# V2.net
KiCad netlist of a schematic drawn in EAGLE
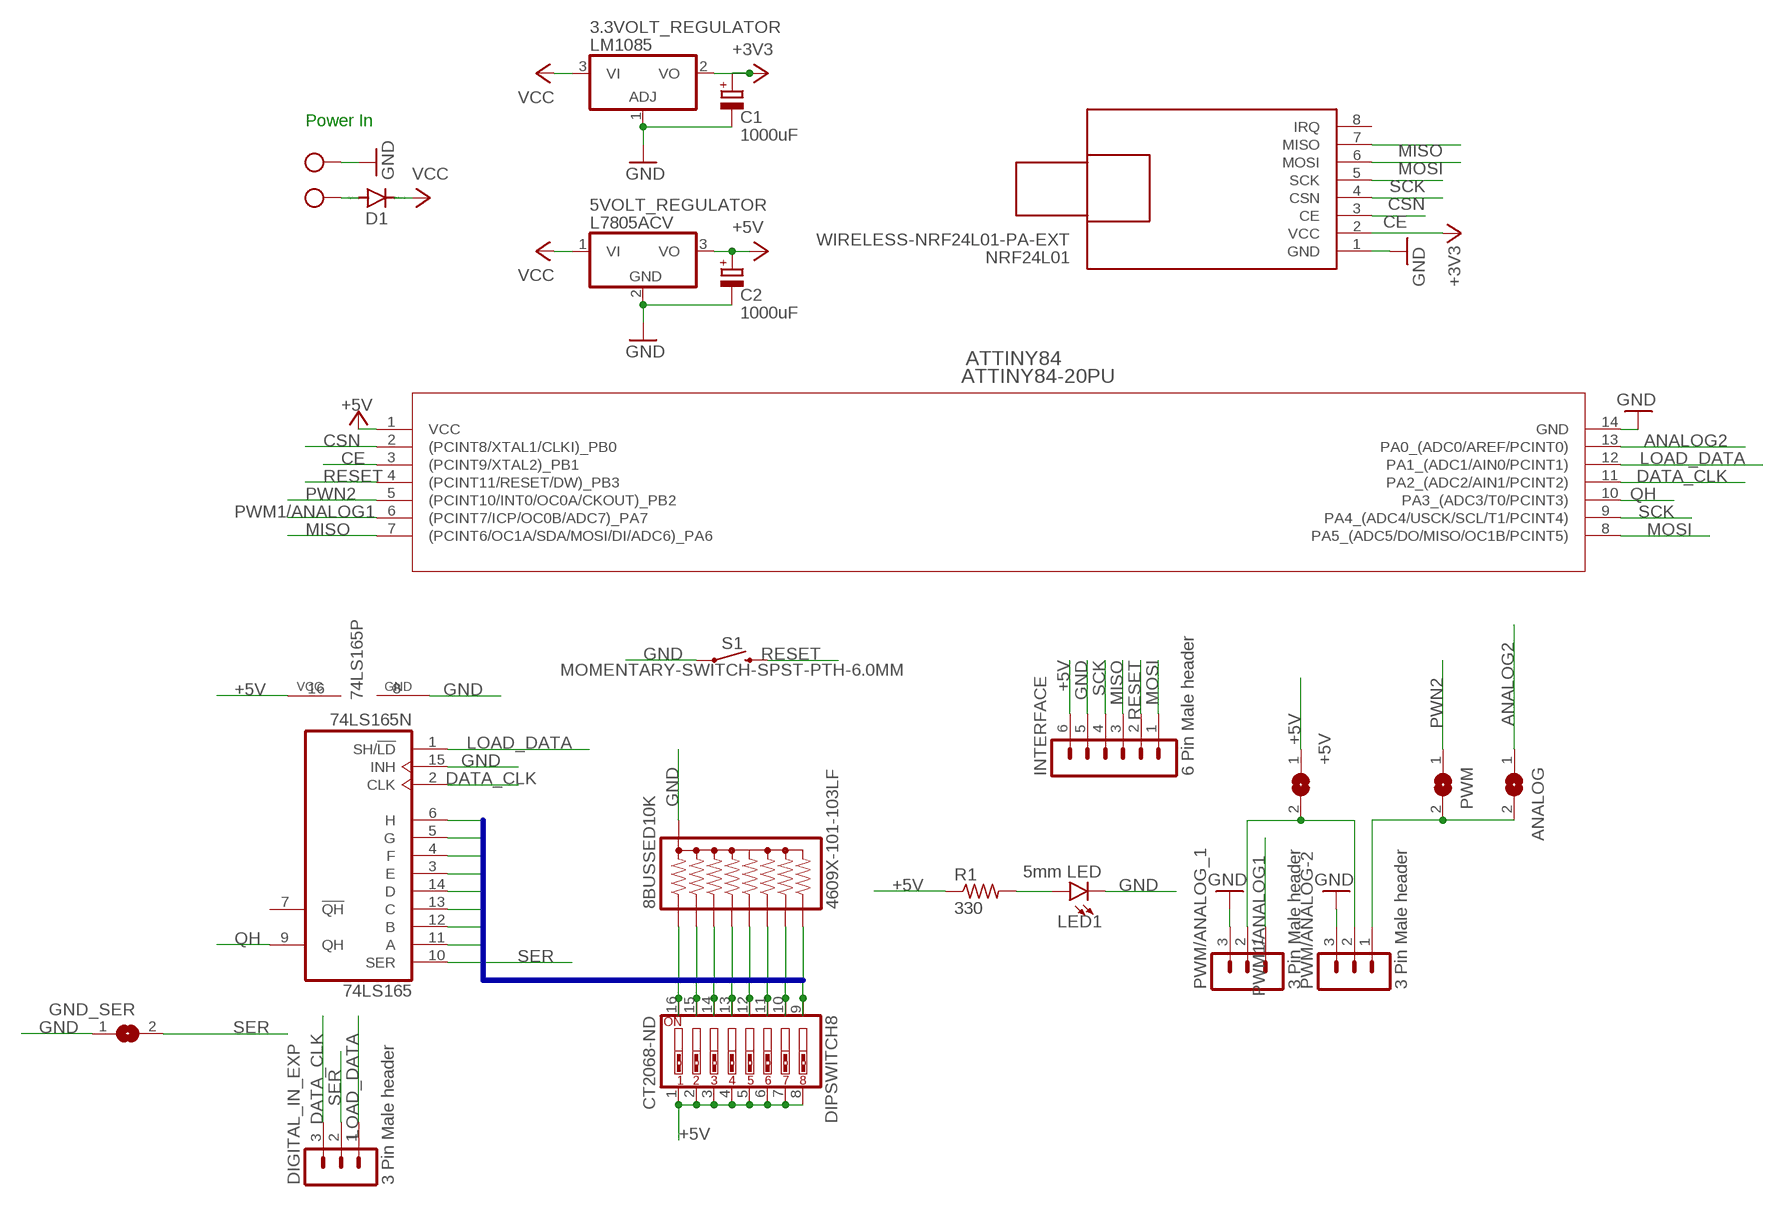
[diagram p0: schematic, sheet 1]

(export (version "E")
  (design (tool "Eeschema 10.0.6"))
  (components
    (comp (ref "+5V")
      (value "SJW")
      (footprint "eagle-import:SJW")
      (libsource (lib "eagle-import") (part "SJW"))
    )
    (comp (ref "3.3VOLT_REGULATOR")
      (value "LM1085")
      (footprint "eagle-import:TO220V")
      (libsource (lib "eagle-import") (part "MC33269?T-12"))
    )
    (comp (ref "5VOLT_REGULATOR")
      (value "L7805ACV")
      (footprint "eagle-import:TO220V")
      (libsource (lib "eagle-import") (part "78TV8"))
    )
    (comp (ref "8BUSSED10K")
      (value "4609X-101-103LF")
      (footprint "eagle-import:RPACK-SIP-PTH-8")
      (libsource (lib "eagle-import") (part "10K_BUSSED_8"))
    )
    (comp (ref "74LS165")
      (value "74LS165N")
      (footprint "eagle-import:DIL16")
      (libsource (lib "eagle-import") (part "74165NLS"))
    )
    (comp (ref "ANALOG")
      (value "SJW")
      (footprint "eagle-import:SJW")
      (libsource (lib "eagle-import") (part "SJW"))
    )
    (comp (ref "ATTINY84")
      (value "ATTINY84-20PU")
      (footprint "eagle-import:14P3")
      (fields (field (name "MANUFACTURER_PART_NUMBER") "ATTINY8420PU"))
      (libsource (lib "eagle-import") (part "ATTINY84-20PU"))
    )
    (comp (ref "C1")
      (value "1000uF")
      (footprint "eagle-import:E2,5-6")
      (libsource (lib "eagle-import") (part "CPOL-EUE2.5-6"))
    )
    (comp (ref "C2")
      (value "1000uF")
      (footprint "eagle-import:E2,5-6")
      (libsource (lib "eagle-import") (part "CPOL-EUE2.5-6"))
    )
    (comp (ref "D1")
      (value "1N5060GP")
      (footprint "eagle-import:DO15-12")
      (libsource (lib "eagle-import") (part "1N5060GP"))
    )
    (comp (ref "DIGITAL_IN_EXP")
      (value "3 Pin Male header")
      (footprint "eagle-import:MA03-1")
      (libsource (lib "eagle-import") (part "MA03-1"))
    )
    (comp (ref "DIPSWITCH8")
      (value "CT2068-ND")
      (footprint "eagle-import:EDG-08")
      (libsource (lib "eagle-import") (part "SW_DIP-8"))
    )
    (comp (ref "GND_SER")
      (value "SJW")
      (footprint "eagle-import:SJW")
      (libsource (lib "eagle-import") (part "SJW"))
    )
    (comp (ref "INTERFACE")
      (value "6 Pin Male header")
      (footprint "eagle-import:MA06-1")
      (libsource (lib "eagle-import") (part "MA06-1"))
    )
    (comp (ref "LED1")
      (value "5mm LED")
      (footprint "eagle-import:LED_5MM")
      (libsource (lib "eagle-import") (part "LED5MM"))
    )
    (comp (ref "NRF24L01")
      (value "WIRELESS-NRF24L01-PA-EXT")
      (footprint "eagle-import:WIRELESS-NRF24L01-PA-EXT")
      (libsource (lib "eagle-import") (part "WIRELESS-NRF24L01-PA-EXT"))
    )
    (comp (ref "PWM")
      (value "SJW")
      (footprint "eagle-import:SJW")
      (libsource (lib "eagle-import") (part "SJW"))
    )
    (comp (ref "PWM/ANALOG-2")
      (value "3 Pin Male header")
      (footprint "eagle-import:MA03-1")
      (libsource (lib "eagle-import") (part "MA03-1"))
    )
    (comp (ref "PWM/ANALOG_1")
      (value "3 Pin Male header")
      (footprint "eagle-import:MA03-1")
      (libsource (lib "eagle-import") (part "MA03-1"))
    )
    (comp (ref "R1")
      (value "330")
      (footprint "eagle-import:0204_7")
      (libsource (lib "eagle-import") (part "R-US_0204/7"))
    )
    (comp (ref "S1")
      (value "MOMENTARY-SWITCH-SPST-PTH-6.0MM")
      (footprint "eagle-import:TACTILE_SWITCH_PTH_6.0MM")
      (libsource (lib "eagle-import") (part "MOMENTARY-SWITCH-SPST-PTH-6.0MM"))
    )
    (comp (ref "X1")
      (value "MKDSN1,5/2-5,08")
      (footprint "eagle-import:MKDSN1,5_2-5,08")
      (libsource (lib "eagle-import") (part "MKDSN1,5/2-5,08"))
    )
  )
  (nets
    (net (code "1") (name "+3V3") (class "Default")
      (node (ref "3.3VOLT_REGULATOR") (pin "2") (pinfunction "VO_2") (pintype "passive"))
      (node (ref "C1") (pin "+") (pinfunction "+_+") (pintype "passive"))
      (node (ref "NRF24L01") (pin "2") (pinfunction "VCC_2") (pintype "power_in"))
    )
    (net (code "2") (name "+5V") (class "Default")
      (node (ref "+5V") (pin "1") (pinfunction "1_1") (pintype "passive"))
      (node (ref "5VOLT_REGULATOR") (pin "3") (pinfunction "VO_3") (pintype "passive"))
      (node (ref "74LS165") (pin "16") (pinfunction "VCC_16") (pintype "power_in"))
      (node (ref "ATTINY84") (pin "1") (pinfunction "VCC_1") (pintype "power_in"))
      (node (ref "C2") (pin "+") (pinfunction "+_+") (pintype "passive"))
      (node (ref "DIPSWITCH8") (pin "1") (pinfunction "1_1") (pintype "passive"))
      (node (ref "DIPSWITCH8") (pin "2") (pinfunction "2_2") (pintype "passive"))
      (node (ref "DIPSWITCH8") (pin "3") (pinfunction "3_3") (pintype "passive"))
      (node (ref "DIPSWITCH8") (pin "4") (pinfunction "4_4") (pintype "passive"))
      (node (ref "DIPSWITCH8") (pin "5") (pinfunction "5_5") (pintype "passive"))
      (node (ref "DIPSWITCH8") (pin "6") (pinfunction "6_6") (pintype "passive"))
      (node (ref "DIPSWITCH8") (pin "7") (pinfunction "7_7") (pintype "passive"))
      (node (ref "DIPSWITCH8") (pin "8") (pinfunction "8_8") (pintype "passive"))
      (node (ref "INTERFACE") (pin "6") (pinfunction "6_6") (pintype "passive"))
      (node (ref "R1") (pin "1") (pinfunction "1_1") (pintype "passive"))
    )
    (net (code "3") (name "/ANALOG2") (class "Default")
      (node (ref "ANALOG") (pin "1") (pinfunction "1_1") (pintype "passive"))
      (node (ref "ATTINY84") (pin "13") (pinfunction "PA0_(ADC0/AREF/PCINT0)_13") (pintype "bidirectional"))
    )
    (net (code "4") (name "/BIT0") (class "Default")
      (node (ref "74LS165") (pin "11") (pinfunction "A_11") (pintype "input"))
      (node (ref "8BUSSED10K") (pin "P$2") (pinfunction "2_P$2") (pintype "passive"))
      (node (ref "DIPSWITCH8") (pin "16") (pinfunction "16_16") (pintype "passive"))
    )
    (net (code "5") (name "/BIT1") (class "Default")
      (node (ref "74LS165") (pin "12") (pinfunction "B_12") (pintype "input"))
      (node (ref "8BUSSED10K") (pin "P$3") (pinfunction "3_P$3") (pintype "passive"))
      (node (ref "DIPSWITCH8") (pin "15") (pinfunction "15_15") (pintype "passive"))
    )
    (net (code "6") (name "/BIT2") (class "Default")
      (node (ref "74LS165") (pin "13") (pinfunction "C_13") (pintype "input"))
      (node (ref "8BUSSED10K") (pin "P$4") (pinfunction "4_P$4") (pintype "passive"))
      (node (ref "DIPSWITCH8") (pin "14") (pinfunction "14_14") (pintype "passive"))
    )
    (net (code "7") (name "/BIT3") (class "Default")
      (node (ref "74LS165") (pin "14") (pinfunction "D_14") (pintype "input"))
      (node (ref "8BUSSED10K") (pin "P$5") (pinfunction "5_P$5") (pintype "passive"))
      (node (ref "DIPSWITCH8") (pin "13") (pinfunction "13_13") (pintype "passive"))
    )
    (net (code "8") (name "/BIT4") (class "Default")
      (node (ref "74LS165") (pin "3") (pinfunction "E_3") (pintype "input"))
      (node (ref "8BUSSED10K") (pin "P$6") (pinfunction "6_P$6") (pintype "passive"))
      (node (ref "DIPSWITCH8") (pin "12") (pinfunction "12_12") (pintype "passive"))
    )
    (net (code "9") (name "/BIT5") (class "Default")
      (node (ref "74LS165") (pin "4") (pinfunction "F_4") (pintype "input"))
      (node (ref "8BUSSED10K") (pin "P$7") (pinfunction "7_P$7") (pintype "passive"))
      (node (ref "DIPSWITCH8") (pin "11") (pinfunction "11_11") (pintype "passive"))
    )
    (net (code "10") (name "/BIT6") (class "Default")
      (node (ref "74LS165") (pin "5") (pinfunction "G_5") (pintype "input"))
      (node (ref "8BUSSED10K") (pin "P$8") (pinfunction "8_P$8") (pintype "passive"))
      (node (ref "DIPSWITCH8") (pin "10") (pinfunction "10_10") (pintype "passive"))
    )
    (net (code "11") (name "/BIT7") (class "Default")
      (node (ref "74LS165") (pin "6") (pinfunction "H_6") (pintype "input"))
      (node (ref "8BUSSED10K") (pin "P$9") (pinfunction "9_P$9") (pintype "passive"))
      (node (ref "DIPSWITCH8") (pin "9") (pinfunction "9_9") (pintype "passive"))
    )
    (net (code "12") (name "/CE") (class "Default")
      (node (ref "ATTINY84") (pin "3") (pinfunction "(PCINT9/XTAL2)_PB1_3") (pintype "bidirectional"))
      (node (ref "NRF24L01") (pin "3") (pinfunction "CE_3") (pintype "bidirectional"))
    )
    (net (code "13") (name "/CSN") (class "Default")
      (node (ref "ATTINY84") (pin "2") (pinfunction "(PCINT8/XTAL1/CLKI)_PB0_2") (pintype "bidirectional"))
      (node (ref "NRF24L01") (pin "4") (pinfunction "CSN_4") (pintype "bidirectional"))
    )
    (net (code "14") (name "/DATA_CLK") (class "Default")
      (node (ref "74LS165") (pin "2") (pinfunction "CLK_2") (pintype "input"))
      (node (ref "ATTINY84") (pin "11") (pinfunction "PA2_(ADC2/AIN1/PCINT2)_11") (pintype "bidirectional"))
      (node (ref "DIGITAL_IN_EXP") (pin "3") (pinfunction "3_3") (pintype "passive"))
    )
    (net (code "15") (name "/LOAD_DATA") (class "Default")
      (node (ref "74LS165") (pin "1") (pinfunction "SH/~{LD}_1") (pintype "input"))
      (node (ref "ATTINY84") (pin "12") (pinfunction "PA1_(ADC1/AIN0/PCINT1)_12") (pintype "bidirectional"))
      (node (ref "DIGITAL_IN_EXP") (pin "1") (pinfunction "1_1") (pintype "passive"))
    )
    (net (code "16") (name "/MISO") (class "Default")
      (node (ref "ATTINY84") (pin "7") (pinfunction "(PCINT6/OC1A/SDA/MOSI/DI/ADC6)_PA6_7") (pintype "bidirectional"))
      (node (ref "INTERFACE") (pin "3") (pinfunction "3_3") (pintype "passive"))
      (node (ref "NRF24L01") (pin "7") (pinfunction "MISO_7") (pintype "bidirectional"))
    )
    (net (code "17") (name "/MOSI") (class "Default")
      (node (ref "ATTINY84") (pin "8") (pinfunction "PA5_(ADC5/DO/MISO/OC1B/PCINT5)_8") (pintype "bidirectional"))
      (node (ref "INTERFACE") (pin "1") (pinfunction "1_1") (pintype "passive"))
      (node (ref "NRF24L01") (pin "6") (pinfunction "MOSI_6") (pintype "bidirectional"))
    )
    (net (code "18") (name "/PWM1{slash}ANALOG1") (class "Default")
      (node (ref "ATTINY84") (pin "6") (pinfunction "(PCINT7/ICP/OC0B/ADC7)_PA7_6") (pintype "bidirectional"))
      (node (ref "PWM/ANALOG_1") (pin "1") (pinfunction "1_1") (pintype "passive"))
    )
    (net (code "19") (name "/PWN2") (class "Default")
      (node (ref "ATTINY84") (pin "5") (pinfunction "(PCINT10/INT0/OC0A/CKOUT)_PB2_5") (pintype "bidirectional"))
      (node (ref "PWM") (pin "1") (pinfunction "1_1") (pintype "passive"))
    )
    (net (code "20") (name "/QH") (class "Default")
      (node (ref "74LS165") (pin "9") (pinfunction "QH_9") (pintype "output"))
      (node (ref "ATTINY84") (pin "10") (pinfunction "PA3_(ADC3/T0/PCINT3)_10") (pintype "bidirectional"))
    )
    (net (code "21") (name "/RESET") (class "Default")
      (node (ref "ATTINY84") (pin "4") (pinfunction "(PCINT11/RESET/DW)_PB3_4") (pintype "bidirectional"))
      (node (ref "INTERFACE") (pin "2") (pinfunction "2_2") (pintype "passive"))
      (node (ref "S1") (pin "3") (pinfunction "2_3") (pintype "passive"))
    )
    (net (code "22") (name "/SCK") (class "Default")
      (node (ref "ATTINY84") (pin "9") (pinfunction "PA4_(ADC4/USCK/SCL/T1/PCINT4)_9") (pintype "bidirectional"))
      (node (ref "INTERFACE") (pin "4") (pinfunction "4_4") (pintype "passive"))
      (node (ref "NRF24L01") (pin "5") (pinfunction "SCK_5") (pintype "bidirectional"))
    )
    (net (code "23") (name "/SER") (class "Default")
      (node (ref "74LS165") (pin "10") (pinfunction "SER_10") (pintype "input"))
      (node (ref "DIGITAL_IN_EXP") (pin "2") (pinfunction "2_2") (pintype "passive"))
      (node (ref "GND_SER") (pin "2") (pinfunction "2_2") (pintype "passive"))
    )
    (net (code "24") (name "GND") (class "Default")
      (node (ref "3.3VOLT_REGULATOR") (pin "1") (pinfunction "ADJ_1") (pintype "input"))
      (node (ref "5VOLT_REGULATOR") (pin "2") (pinfunction "GND_2") (pintype "passive"))
      (node (ref "74LS165") (pin "15") (pinfunction "INH_15") (pintype "input"))
      (node (ref "74LS165") (pin "8") (pinfunction "GND_8") (pintype "power_in"))
      (node (ref "8BUSSED10K") (pin "P$1") (pinfunction "1_P$1") (pintype "passive"))
      (node (ref "ATTINY84") (pin "14") (pinfunction "GND_14") (pintype "power_in"))
      (node (ref "C1") (pin "-") (pinfunction "-_-") (pintype "passive"))
      (node (ref "C2") (pin "-") (pinfunction "-_-") (pintype "passive"))
      (node (ref "GND_SER") (pin "1") (pinfunction "1_1") (pintype "passive"))
      (node (ref "INTERFACE") (pin "5") (pinfunction "5_5") (pintype "passive"))
      (node (ref "LED1") (pin "K") (pinfunction "C_K") (pintype "passive"))
      (node (ref "NRF24L01") (pin "1") (pinfunction "GND_1") (pintype "power_in"))
      (node (ref "PWM/ANALOG-2") (pin "3") (pinfunction "3_3") (pintype "passive"))
      (node (ref "PWM/ANALOG_1") (pin "3") (pinfunction "3_3") (pintype "passive"))
      (node (ref "S1") (pin "1") (pinfunction "1_1") (pintype "passive"))
      (node (ref "X1") (pin "2") (pinfunction "KL_2") (pintype "passive"))
    )
    (net (code "25") (name "Net-(+5V-Pad2)") (class "Default")
      (node (ref "+5V") (pin "2") (pinfunction "2_2") (pintype "passive"))
      (node (ref "PWM/ANALOG-2") (pin "2") (pinfunction "2_2") (pintype "passive"))
      (node (ref "PWM/ANALOG_1") (pin "2") (pinfunction "2_2") (pintype "passive"))
    )
    (net (code "26") (name "Net-(ANALOG-Pad2)") (class "Default")
      (node (ref "ANALOG") (pin "2") (pinfunction "2_2") (pintype "passive"))
      (node (ref "PWM") (pin "2") (pinfunction "2_2") (pintype "passive"))
      (node (ref "PWM/ANALOG-2") (pin "1") (pinfunction "1_1") (pintype "passive"))
    )
    (net (code "27") (name "Net-(LED1-PadA)") (class "Default")
      (node (ref "LED1") (pin "A") (pinfunction "A_A") (pintype "passive"))
      (node (ref "R1") (pin "2") (pinfunction "2_2") (pintype "passive"))
    )
    (net (code "28") (name "Net-(X1A-KL)") (class "Default")
      (node (ref "D1") (pin "A") (pinfunction "A_A") (pintype "passive"))
      (node (ref "X1") (pin "1") (pinfunction "KL_1") (pintype "passive"))
    )
    (net (code "29") (name "VCC") (class "Default")
      (node (ref "3.3VOLT_REGULATOR") (pin "3") (pinfunction "VI_3") (pintype "input"))
      (node (ref "5VOLT_REGULATOR") (pin "1") (pinfunction "VI_1") (pintype "input"))
      (node (ref "D1") (pin "C") (pinfunction "C_C") (pintype "passive"))
    )
    (net (code "30") (name "unconnected-(74LS165A-~{QH}-Pad7)") (class "Default")
      (node (ref "74LS165") (pin "7") (pinfunction "~{QH}_7") (pintype "output"))
    )
    (net (code "31") (name "unconnected-(NRF24L01-IRQ-Pad8)") (class "Default")
      (node (ref "NRF24L01") (pin "8") (pinfunction "IRQ_8") (pintype "bidirectional"))
    )
  )
)
